# controller.net
KiCad netlist of a schematic drawn in Altium Designer
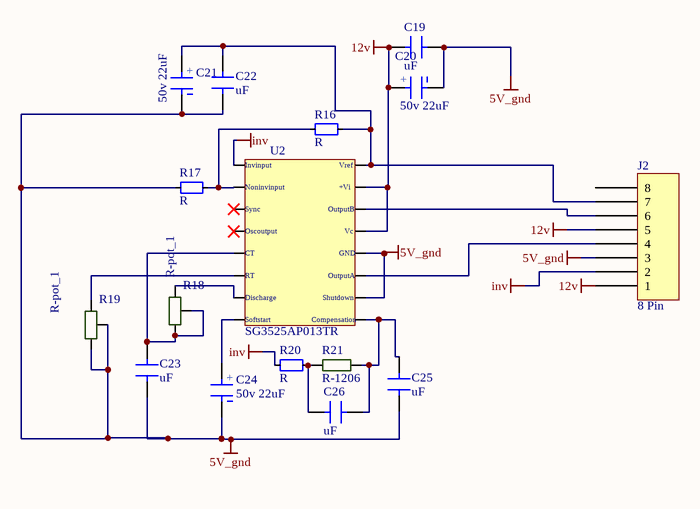
[diagram p0: controller.SchDoc]

(export (version "E")
  (design (tool "Eeschema 10.0.6"))
  (components
    (comp (ref "C19") (value "uF") (footprint "C-1206") (libsource (lib "SMPSProject") (part "C-1206")))
    (comp (ref "C20")
      (value "50v 22uF")
      (footprint "50v 22uf")
      (fields
        (field (name "MANUFACTURER") "Nichicon")
        (field (name "MANUFACTURER PART NUMBER") "LKS1J472MESZ")
        (field (name "TOLERANCE") "20%")
      )
      (libsource (lib "SMPSProject") (part "50v 22uF"))
    )
    (comp (ref "C21")
      (value "50v 22uF")
      (footprint "50v 22uf")
      (fields
        (field (name "MANUFACTURER") "Nichicon")
        (field (name "MANUFACTURER PART NUMBER") "LKS1J472MESZ")
        (field (name "TOLERANCE") "20%")
      )
      (libsource (lib "SMPSProject") (part "50v 22uF"))
    )
    (comp (ref "C22") (value "uF") (footprint "C-1206") (libsource (lib "SMPSProject") (part "C-1206")))
    (comp (ref "C23") (value "uF") (footprint "C-1206") (libsource (lib "SMPSProject") (part "C-1206")))
    (comp (ref "C24")
      (value "50v 22uF")
      (footprint "50v 22uf")
      (fields
        (field (name "MANUFACTURER") "Nichicon")
        (field (name "MANUFACTURER PART NUMBER") "LKS1J472MESZ")
        (field (name "TOLERANCE") "20%")
      )
      (libsource (lib "SMPSProject") (part "50v 22uF"))
    )
    (comp (ref "C25") (value "uF") (footprint "C-1206") (libsource (lib "SMPSProject") (part "C-1206")))
    (comp (ref "C26") (value "uF") (footprint "C-1206") (libsource (lib "SMPSProject") (part "C-1206")))
    (comp (ref "J2")
      (value "8 Pin")
      (footprint "8 pin connector")
      (libsource (lib "SMPSProject") (part "8 Pin"))
    )
    (comp (ref "R16") (value "R") (footprint "R-0805R") (libsource (lib "SMPSProject") (part "R 0805")))
    (comp (ref "R17") (value "R") (footprint "R-0805R") (libsource (lib "SMPSProject") (part "R 0805")))
    (comp (ref "R18")
      (value "R-pot_1")
      (footprint "pot")
      (description "Res1206")
      (libsource (lib "SMPSProject") (part "R-pot_1"))
    )
    (comp (ref "R19")
      (value "R-pot_1")
      (footprint "pot")
      (description "Res1206")
      (libsource (lib "SMPSProject") (part "R-pot_1"))
    )
    (comp (ref "R20") (value "R") (footprint "R-0805R") (libsource (lib "SMPSProject") (part "R 0805")))
    (comp (ref "R21")
      (value "R-1206")
      (footprint "R-1206")
      (description "Res1206")
      (libsource (lib "SMPSProject") (part "R-1206"))
    )
    (comp (ref "U2")
      (value "SG3525AP013TR")
      (footprint "SOIC16N SG3525")
      (description "IC REG CTRLR BCK/PSH-PULL 16SOIC")
      (fields (field (name "MANUFACTURER") "STMicroelectronics"))
      (libsource (lib "SMPSProject") (part "SG3525AP013TR"))
    )
  )
  (nets
    (net (code "1") (name "5V_gnd") (class "Default")
      (node (ref "C19") (pin "1") (pinfunction "1_1") (pintype "passive"))
      (node (ref "C20") (pin "2") (pinfunction "2_2") (pintype "passive"))
      (node (ref "C21") (pin "2") (pinfunction "2_2") (pintype "passive"))
      (node (ref "C22") (pin "2") (pinfunction "2_2") (pintype "passive"))
      (node (ref "C23") (pin "1") (pinfunction "1_1") (pintype "passive"))
      (node (ref "C24") (pin "2") (pinfunction "2_2") (pintype "passive"))
      (node (ref "C25") (pin "2") (pinfunction "2_2") (pintype "passive"))
      (node (ref "J2") (pin "3") (pinfunction "3_3") (pintype "passive"))
      (node (ref "R17") (pin "1") (pinfunction "1_1") (pintype "passive"))
      (node (ref "R19") (pin "1") (pinfunction "1_1") (pintype "passive"))
      (node (ref "R19") (pin "2") (pinfunction "2_2") (pintype "passive"))
      (node (ref "U2") (pin "10") (pinfunction "10_10") (pintype "passive"))
      (node (ref "U2") (pin "12") (pinfunction "12_12") (pintype "passive"))
    )
    (net (code "2") (name "12v") (class "Default")
      (node (ref "C19") (pin "2") (pinfunction "2_2") (pintype "passive"))
      (node (ref "C20") (pin "1") (pinfunction "1_1") (pintype "passive"))
      (node (ref "J2") (pin "1") (pinfunction "1_1") (pintype "passive"))
      (node (ref "J2") (pin "5") (pinfunction "5_5") (pintype "passive"))
      (node (ref "U2") (pin "13") (pinfunction "13_13") (pintype "passive"))
      (node (ref "U2") (pin "15") (pinfunction "15_15") (pintype "passive"))
    )
    (net (code "3") (name "Net-(C21-Pad1)") (class "Default")
      (node (ref "C21") (pin "1") (pinfunction "1_1") (pintype "passive"))
      (node (ref "C22") (pin "1") (pinfunction "1_1") (pintype "passive"))
      (node (ref "J2") (pin "7") (pinfunction "7_7") (pintype "passive"))
      (node (ref "R16") (pin "2") (pinfunction "2_2") (pintype "passive"))
      (node (ref "U2") (pin "16") (pinfunction "16_16") (pintype "passive"))
    )
    (net (code "4") (name "Net-(C23-Pad2)") (class "Default")
      (node (ref "C23") (pin "2") (pinfunction "2_2") (pintype "passive"))
      (node (ref "R18") (pin "1") (pinfunction "1_1") (pintype "passive"))
      (node (ref "R18") (pin "2") (pinfunction "2_2") (pintype "passive"))
      (node (ref "U2") (pin "5") (pinfunction "5_5") (pintype "passive"))
    )
    (net (code "5") (name "Net-(C24-Pad1)") (class "Default")
      (node (ref "C24") (pin "1") (pinfunction "1_1") (pintype "passive"))
      (node (ref "U2") (pin "8") (pinfunction "8_8") (pintype "passive"))
    )
    (net (code "6") (name "Net-(C25-Pad1)") (class "Default")
      (node (ref "C25") (pin "1") (pinfunction "1_1") (pintype "passive"))
      (node (ref "C26") (pin "2") (pinfunction "2_2") (pintype "passive"))
      (node (ref "R21") (pin "2") (pinfunction "2_2") (pintype "passive"))
      (node (ref "U2") (pin "9") (pinfunction "9_9") (pintype "passive"))
    )
    (net (code "7") (name "Net-(C26-Pad1)") (class "Default")
      (node (ref "C26") (pin "1") (pinfunction "1_1") (pintype "passive"))
      (node (ref "R20") (pin "2") (pinfunction "2_2") (pintype "passive"))
      (node (ref "R21") (pin "1") (pinfunction "1_1") (pintype "passive"))
    )
    (net (code "8") (name "Net-(J2-Pad4)") (class "Default")
      (node (ref "J2") (pin "4") (pinfunction "4_4") (pintype "passive"))
      (node (ref "U2") (pin "11") (pinfunction "11_11") (pintype "passive"))
    )
    (net (code "9") (name "Net-(J2-Pad6)") (class "Default")
      (node (ref "J2") (pin "6") (pinfunction "6_6") (pintype "passive"))
      (node (ref "U2") (pin "14") (pinfunction "14_14") (pintype "passive"))
    )
    (net (code "10") (name "Net-(R16-Pad1)") (class "Default")
      (node (ref "R16") (pin "1") (pinfunction "1_1") (pintype "passive"))
      (node (ref "R17") (pin "2") (pinfunction "2_2") (pintype "passive"))
      (node (ref "U2") (pin "2") (pinfunction "2_2") (pintype "passive"))
    )
    (net (code "11") (name "Net-(R18-Pad3)") (class "Default")
      (node (ref "R18") (pin "3") (pinfunction "3_3") (pintype "passive"))
      (node (ref "U2") (pin "7") (pinfunction "7_7") (pintype "passive"))
    )
    (net (code "12") (name "Net-(R19-Pad3)") (class "Default")
      (node (ref "R19") (pin "3") (pinfunction "3_3") (pintype "passive"))
      (node (ref "U2") (pin "6") (pinfunction "6_6") (pintype "passive"))
    )
    (net (code "13") (name "inv") (class "Default")
      (node (ref "J2") (pin "2") (pinfunction "2_2") (pintype "passive"))
      (node (ref "R20") (pin "1") (pinfunction "1_1") (pintype "passive"))
      (node (ref "U2") (pin "1") (pinfunction "1_1") (pintype "passive"))
    )
    (net (code "14") (name "unconnected-(J2-Pad8)") (class "Default")
      (node (ref "J2") (pin "8") (pinfunction "8_8") (pintype "passive"))
    )
    (net (code "15") (name "unconnected-(U2-Pad3)") (class "Default")
      (node (ref "U2") (pin "3") (pinfunction "3_3") (pintype "passive+no_connect"))
    )
    (net (code "16") (name "unconnected-(U2-Pad4)") (class "Default")
      (node (ref "U2") (pin "4") (pinfunction "4_4") (pintype "passive+no_connect"))
    )
  )
)
